# Address_Buffer_0_2.net
KiCad netlist of a schematic drawn in EasyEDA Pro
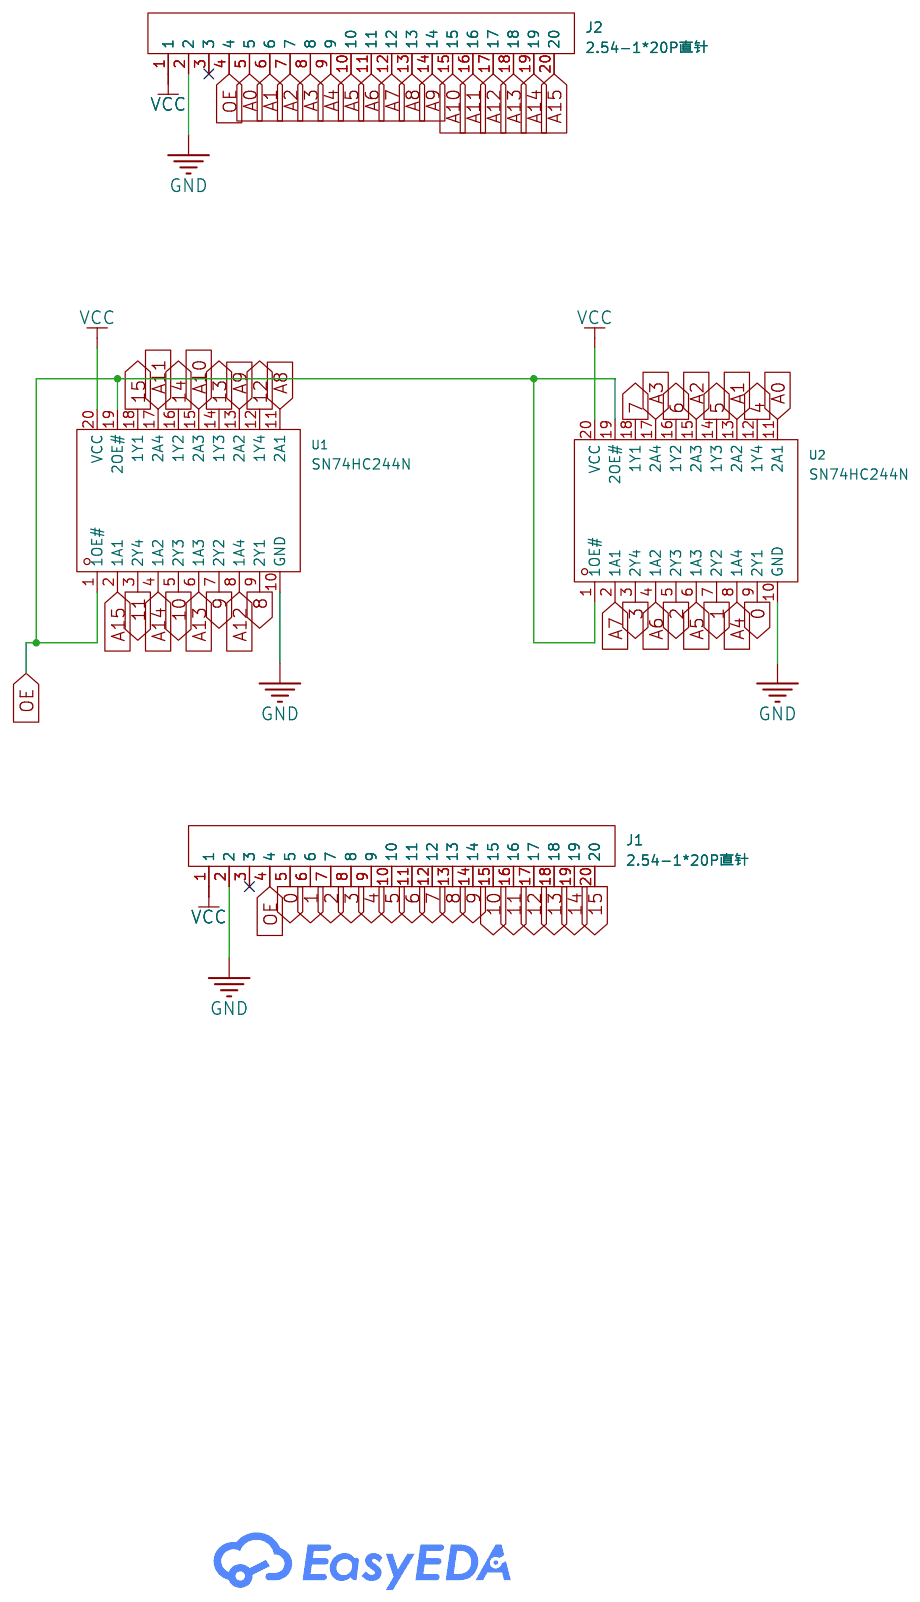
[diagram p0: schematic sheet]

(export (version "E")
  (design (tool "Eeschema 10.0.6"))
  (components
    (comp (ref "J1")
      (value "2.54-1*20P直针")
      (footprint "easyedapro:HDR-TH_20P-P2.54-V-M-1")
      (fields (field (name "Manufacturer") "BOOMELE(博穆精密)"))
      (libsource (lib "easyedapro") (part "Header-Male-2.54_1x20"))
    )
    (comp (ref "J2")
      (value "2.54-1*20P直针")
      (footprint "easyedapro:HDR-TH_20P-P2.54-V-M-1")
      (fields (field (name "Manufacturer") "BOOMELE(博穆精密)"))
      (libsource (lib "easyedapro") (part "Header-Male-2.54_1x20"))
    )
    (comp (ref "U1")
      (value "SN74HC244N")
      (footprint "easyedapro:DIP-20_L26.8-W6.4-P2.54-LS7.6-BL")
      (fields (field (name "Manufacturer") "TI(德州仪器)"))
      (libsource (lib "easyedapro") (part "SN74HC244N"))
    )
    (comp (ref "U2")
      (value "SN74HC244N")
      (footprint "easyedapro:DIP-20_L26.8-W6.4-P2.54-LS7.6-BL")
      (fields (field (name "Manufacturer") "TI(德州仪器)"))
      (libsource (lib "easyedapro") (part "SN74HC244N"))
    )
  )
  (nets
    (net (code "1") (name "0") (class "Default")
      (node (ref "J1") (pin "5") (pinfunction "5_5") (pintype "unspecified"))
      (node (ref "U2") (pin "9") (pinfunction "2Y1_9") (pintype "input"))
    )
    (net (code "2") (name "1") (class "Default")
      (node (ref "J1") (pin "6") (pinfunction "6_6") (pintype "unspecified"))
      (node (ref "U2") (pin "7") (pinfunction "2Y2_7") (pintype "input"))
    )
    (net (code "3") (name "2") (class "Default")
      (node (ref "J1") (pin "7") (pinfunction "7_7") (pintype "unspecified"))
      (node (ref "U2") (pin "5") (pinfunction "2Y3_5") (pintype "input"))
    )
    (net (code "4") (name "3") (class "Default")
      (node (ref "J1") (pin "8") (pinfunction "8_8") (pintype "unspecified"))
      (node (ref "U2") (pin "3") (pinfunction "2Y4_3") (pintype "input"))
    )
    (net (code "5") (name "4") (class "Default")
      (node (ref "J1") (pin "9") (pinfunction "9_9") (pintype "unspecified"))
      (node (ref "U2") (pin "12") (pinfunction "1Y4_12") (pintype "input"))
    )
    (net (code "6") (name "5") (class "Default")
      (node (ref "J1") (pin "10") (pinfunction "10_10") (pintype "unspecified"))
      (node (ref "U2") (pin "14") (pinfunction "1Y3_14") (pintype "input"))
    )
    (net (code "7") (name "6") (class "Default")
      (node (ref "J1") (pin "11") (pinfunction "11_11") (pintype "unspecified"))
      (node (ref "U2") (pin "16") (pinfunction "1Y2_16") (pintype "input"))
    )
    (net (code "8") (name "7") (class "Default")
      (node (ref "J1") (pin "12") (pinfunction "12_12") (pintype "unspecified"))
      (node (ref "U2") (pin "18") (pinfunction "1Y1_18") (pintype "input"))
    )
    (net (code "9") (name "8") (class "Default")
      (node (ref "J1") (pin "13") (pinfunction "13_13") (pintype "unspecified"))
      (node (ref "U1") (pin "9") (pinfunction "2Y1_9") (pintype "input"))
    )
    (net (code "10") (name "9") (class "Default")
      (node (ref "J1") (pin "14") (pinfunction "14_14") (pintype "unspecified"))
      (node (ref "U1") (pin "7") (pinfunction "2Y2_7") (pintype "input"))
    )
    (net (code "11") (name "10") (class "Default")
      (node (ref "J1") (pin "15") (pinfunction "15_15") (pintype "unspecified"))
      (node (ref "U1") (pin "5") (pinfunction "2Y3_5") (pintype "input"))
    )
    (net (code "12") (name "11") (class "Default")
      (node (ref "J1") (pin "16") (pinfunction "16_16") (pintype "unspecified"))
      (node (ref "U1") (pin "3") (pinfunction "2Y4_3") (pintype "input"))
    )
    (net (code "13") (name "12") (class "Default")
      (node (ref "J1") (pin "17") (pinfunction "17_17") (pintype "unspecified"))
      (node (ref "U1") (pin "12") (pinfunction "1Y4_12") (pintype "input"))
    )
    (net (code "14") (name "13") (class "Default")
      (node (ref "J1") (pin "18") (pinfunction "18_18") (pintype "unspecified"))
      (node (ref "U1") (pin "14") (pinfunction "1Y3_14") (pintype "input"))
    )
    (net (code "15") (name "14") (class "Default")
      (node (ref "J1") (pin "19") (pinfunction "19_19") (pintype "unspecified"))
      (node (ref "U1") (pin "16") (pinfunction "1Y2_16") (pintype "input"))
    )
    (net (code "16") (name "15") (class "Default")
      (node (ref "J1") (pin "20") (pinfunction "20_20") (pintype "unspecified"))
      (node (ref "U1") (pin "18") (pinfunction "1Y1_18") (pintype "input"))
    )
    (net (code "17") (name "A0") (class "Default")
      (node (ref "J2") (pin "5") (pinfunction "5_5") (pintype "unspecified"))
      (node (ref "U2") (pin "11") (pinfunction "2A1_11") (pintype "input"))
    )
    (net (code "18") (name "A1") (class "Default")
      (node (ref "J2") (pin "6") (pinfunction "6_6") (pintype "unspecified"))
      (node (ref "U2") (pin "13") (pinfunction "2A2_13") (pintype "input"))
    )
    (net (code "19") (name "A2") (class "Default")
      (node (ref "J2") (pin "7") (pinfunction "7_7") (pintype "unspecified"))
      (node (ref "U2") (pin "15") (pinfunction "2A3_15") (pintype "input"))
    )
    (net (code "20") (name "A3") (class "Default")
      (node (ref "J2") (pin "8") (pinfunction "8_8") (pintype "unspecified"))
      (node (ref "U2") (pin "17") (pinfunction "2A4_17") (pintype "input"))
    )
    (net (code "21") (name "A4") (class "Default")
      (node (ref "J2") (pin "9") (pinfunction "9_9") (pintype "unspecified"))
      (node (ref "U2") (pin "8") (pinfunction "1A4_8") (pintype "input"))
    )
    (net (code "22") (name "A5") (class "Default")
      (node (ref "J2") (pin "10") (pinfunction "10_10") (pintype "unspecified"))
      (node (ref "U2") (pin "6") (pinfunction "1A3_6") (pintype "input"))
    )
    (net (code "23") (name "A6") (class "Default")
      (node (ref "J2") (pin "11") (pinfunction "11_11") (pintype "unspecified"))
      (node (ref "U2") (pin "4") (pinfunction "1A2_4") (pintype "input"))
    )
    (net (code "24") (name "A7") (class "Default")
      (node (ref "J2") (pin "12") (pinfunction "12_12") (pintype "unspecified"))
      (node (ref "U2") (pin "2") (pinfunction "1A1_2") (pintype "input"))
    )
    (net (code "25") (name "A8") (class "Default")
      (node (ref "J2") (pin "13") (pinfunction "13_13") (pintype "unspecified"))
      (node (ref "U1") (pin "11") (pinfunction "2A1_11") (pintype "input"))
    )
    (net (code "26") (name "A9") (class "Default")
      (node (ref "J2") (pin "14") (pinfunction "14_14") (pintype "unspecified"))
      (node (ref "U1") (pin "13") (pinfunction "2A2_13") (pintype "input"))
    )
    (net (code "27") (name "A10") (class "Default")
      (node (ref "J2") (pin "15") (pinfunction "15_15") (pintype "unspecified"))
      (node (ref "U1") (pin "15") (pinfunction "2A3_15") (pintype "input"))
    )
    (net (code "28") (name "A11") (class "Default")
      (node (ref "J2") (pin "16") (pinfunction "16_16") (pintype "unspecified"))
      (node (ref "U1") (pin "17") (pinfunction "2A4_17") (pintype "input"))
    )
    (net (code "29") (name "A12") (class "Default")
      (node (ref "J2") (pin "17") (pinfunction "17_17") (pintype "unspecified"))
      (node (ref "U1") (pin "8") (pinfunction "1A4_8") (pintype "input"))
    )
    (net (code "30") (name "A13") (class "Default")
      (node (ref "J2") (pin "18") (pinfunction "18_18") (pintype "unspecified"))
      (node (ref "U1") (pin "6") (pinfunction "1A3_6") (pintype "input"))
    )
    (net (code "31") (name "A14") (class "Default")
      (node (ref "J2") (pin "19") (pinfunction "19_19") (pintype "unspecified"))
      (node (ref "U1") (pin "4") (pinfunction "1A2_4") (pintype "input"))
    )
    (net (code "32") (name "A15") (class "Default")
      (node (ref "J2") (pin "20") (pinfunction "20_20") (pintype "unspecified"))
      (node (ref "U1") (pin "2") (pinfunction "1A1_2") (pintype "input"))
    )
    (net (code "33") (name "GND") (class "Default")
      (node (ref "J1") (pin "2") (pinfunction "2_2") (pintype "unspecified"))
      (node (ref "J2") (pin "2") (pinfunction "2_2") (pintype "unspecified"))
      (node (ref "U1") (pin "10") (pinfunction "GND_10") (pintype "input"))
      (node (ref "U2") (pin "10") (pinfunction "GND_10") (pintype "input"))
    )
    (net (code "34") (name "OE") (class "Default")
      (node (ref "J1") (pin "4") (pinfunction "4_4") (pintype "unspecified"))
      (node (ref "J2") (pin "4") (pinfunction "4_4") (pintype "unspecified"))
      (node (ref "U1") (pin "1") (pinfunction "1OE#_1") (pintype "input"))
      (node (ref "U1") (pin "19") (pinfunction "2OE#_19") (pintype "input"))
      (node (ref "U2") (pin "1") (pinfunction "1OE#_1") (pintype "input"))
      (node (ref "U2") (pin "19") (pinfunction "2OE#_19") (pintype "input"))
    )
    (net (code "35") (name "VCC") (class "Default")
      (node (ref "J1") (pin "1") (pinfunction "1_1") (pintype "unspecified"))
      (node (ref "J2") (pin "1") (pinfunction "1_1") (pintype "unspecified"))
      (node (ref "U1") (pin "20") (pinfunction "VCC_20") (pintype "input"))
      (node (ref "U2") (pin "20") (pinfunction "VCC_20") (pintype "input"))
    )
    (net (code "36") (name "unconnected-(J1-Pad3)") (class "Default")
      (node (ref "J1") (pin "3") (pinfunction "3_3") (pintype "unspecified+no_connect"))
    )
    (net (code "37") (name "unconnected-(J2-Pad3)") (class "Default")
      (node (ref "J2") (pin "3") (pinfunction "3_3") (pintype "unspecified+no_connect"))
    )
  )
)
